# line_abu2.net
KiCad netlist of a schematic drawn in Altium Designer
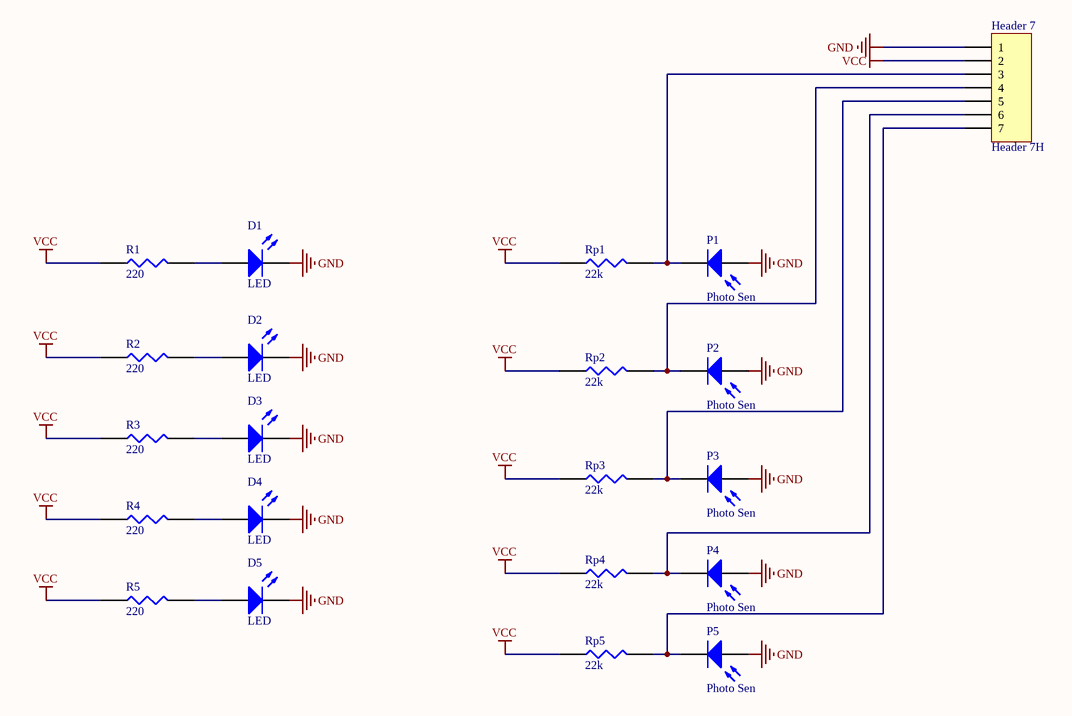
[diagram p0: line abu2.SchDoc]

(export (version "E")
  (design (tool "Eeschema 10.0.6"))
  (components
    (comp (ref "D1")
      (value "LED")
      (footprint "My_LED3MM")
      (description "Typical INFRARED GaAs LED")
      (fields (field (name "PUBLISHER") "Altium Limited"))
      (libsource (lib "Mylib") (part "LED"))
    )
    (comp (ref "D2")
      (value "LED")
      (footprint "My_LED3MM")
      (description "Typical INFRARED GaAs LED")
      (fields (field (name "PUBLISHER") "Altium Limited"))
      (libsource (lib "Mylib") (part "LED"))
    )
    (comp (ref "D3")
      (value "LED")
      (footprint "My_LED3MM")
      (description "Typical INFRARED GaAs LED")
      (fields (field (name "PUBLISHER") "Altium Limited"))
      (libsource (lib "Mylib") (part "LED"))
    )
    (comp (ref "D4")
      (value "LED")
      (footprint "My_LED3MM")
      (description "Typical INFRARED GaAs LED")
      (fields (field (name "PUBLISHER") "Altium Limited"))
      (libsource (lib "Mylib") (part "LED"))
    )
    (comp (ref "D5")
      (value "LED")
      (footprint "My_LED3MM")
      (description "Typical INFRARED GaAs LED")
      (fields (field (name "PUBLISHER") "Altium Limited"))
      (libsource (lib "Mylib") (part "LED"))
    )
    (comp (ref "Header 7")
      (value "Header 7H")
      (footprint "HDR1X7H")
      (description "Header, 7-Pin, Right Angle")
      (fields (field (name "PUBLISHER") "Altium Limited"))
      (libsource (lib "Miscellaneous Connectors") (part "Header 7H"))
    )
    (comp (ref "P1")
      (value "Photo Sen")
      (footprint "PIN2")
      (description "Photosensitive Diode")
      (fields (field (name "PUBLISHER") "Altium Limited"))
      (libsource (lib "Miscellaneous Devices") (part "Photo Sen"))
    )
    (comp (ref "P2")
      (value "Photo Sen")
      (footprint "PIN2")
      (description "Photosensitive Diode")
      (fields (field (name "PUBLISHER") "Altium Limited"))
      (libsource (lib "Miscellaneous Devices") (part "Photo Sen"))
    )
    (comp (ref "P3")
      (value "Photo Sen")
      (footprint "PIN2")
      (description "Photosensitive Diode")
      (fields (field (name "PUBLISHER") "Altium Limited"))
      (libsource (lib "Miscellaneous Devices") (part "Photo Sen"))
    )
    (comp (ref "P4")
      (value "Photo Sen")
      (footprint "PIN2")
      (description "Photosensitive Diode")
      (fields (field (name "PUBLISHER") "Altium Limited"))
      (libsource (lib "Miscellaneous Devices") (part "Photo Sen"))
    )
    (comp (ref "P5")
      (value "Photo Sen")
      (footprint "PIN2")
      (description "Photosensitive Diode")
      (fields (field (name "PUBLISHER") "Altium Limited"))
      (libsource (lib "Miscellaneous Devices") (part "Photo Sen"))
    )
    (comp (ref "R1")
      (value "220")
      (footprint "My_axial-0.4")
      (description "resistor 1/4 wat")
      (fields (field (name "Comment") "1k"))
      (libsource (lib "Mylib") (part "Res"))
    )
    (comp (ref "R2")
      (value "220")
      (footprint "My_axial-0.4")
      (description "resistor 1/4 wat")
      (fields (field (name "Comment") "1k"))
      (libsource (lib "Mylib") (part "Res"))
    )
    (comp (ref "R3")
      (value "220")
      (footprint "My_axial-0.4")
      (description "resistor 1/4 wat")
      (fields (field (name "Comment") "1k"))
      (libsource (lib "Mylib") (part "Res"))
    )
    (comp (ref "R4")
      (value "220")
      (footprint "My_axial-0.4")
      (description "resistor 1/4 wat")
      (fields (field (name "Comment") "1k"))
      (libsource (lib "Mylib") (part "Res"))
    )
    (comp (ref "R5")
      (value "220")
      (footprint "My_axial-0.4")
      (description "resistor 1/4 wat")
      (fields (field (name "Comment") "1k"))
      (libsource (lib "Mylib") (part "Res"))
    )
    (comp (ref "Rp1")
      (value "22k")
      (footprint "My_axial-0.4")
      (description "resistor 1/4 wat")
      (fields (field (name "Comment") "1k"))
      (libsource (lib "Mylib") (part "Res"))
    )
    (comp (ref "Rp2")
      (value "22k")
      (footprint "My_axial-0.4")
      (description "resistor 1/4 wat")
      (fields (field (name "Comment") "1k"))
      (libsource (lib "Mylib") (part "Res"))
    )
    (comp (ref "Rp3")
      (value "22k")
      (footprint "My_axial-0.4")
      (description "resistor 1/4 wat")
      (fields (field (name "Comment") "1k"))
      (libsource (lib "Mylib") (part "Res"))
    )
    (comp (ref "Rp4")
      (value "22k")
      (footprint "My_axial-0.4")
      (description "resistor 1/4 wat")
      (fields (field (name "Comment") "1k"))
      (libsource (lib "Mylib") (part "Res"))
    )
    (comp (ref "Rp5")
      (value "22k")
      (footprint "My_axial-0.4")
      (description "resistor 1/4 wat")
      (fields (field (name "Comment") "1k"))
      (libsource (lib "Mylib") (part "Res"))
    )
  )
  (nets
    (net (code "1") (name "GND") (class "Default")
      (node (ref "D1") (pin "K") (pinfunction "K_K") (pintype "passive"))
      (node (ref "D2") (pin "K") (pinfunction "K_K") (pintype "passive"))
      (node (ref "D3") (pin "K") (pinfunction "K_K") (pintype "passive"))
      (node (ref "D4") (pin "K") (pinfunction "K_K") (pintype "passive"))
      (node (ref "D5") (pin "K") (pinfunction "K_K") (pintype "passive"))
      (node (ref "Header 7") (pin "1") (pinfunction "1_1") (pintype "passive"))
      (node (ref "P1") (pin "1") (pinfunction "A_1") (pintype "passive"))
      (node (ref "P2") (pin "1") (pinfunction "A_1") (pintype "passive"))
      (node (ref "P3") (pin "1") (pinfunction "A_1") (pintype "passive"))
      (node (ref "P4") (pin "1") (pinfunction "A_1") (pintype "passive"))
      (node (ref "P5") (pin "1") (pinfunction "A_1") (pintype "passive"))
    )
    (net (code "2") (name "Net-(D1-PadA)") (class "Default")
      (node (ref "D1") (pin "A") (pinfunction "A_A") (pintype "passive"))
      (node (ref "R1") (pin "2") (pinfunction "2_2") (pintype "passive"))
    )
    (net (code "3") (name "Net-(D2-PadA)") (class "Default")
      (node (ref "D2") (pin "A") (pinfunction "A_A") (pintype "passive"))
      (node (ref "R2") (pin "2") (pinfunction "2_2") (pintype "passive"))
    )
    (net (code "4") (name "Net-(D3-PadA)") (class "Default")
      (node (ref "D3") (pin "A") (pinfunction "A_A") (pintype "passive"))
      (node (ref "R3") (pin "2") (pinfunction "2_2") (pintype "passive"))
    )
    (net (code "5") (name "Net-(D4-PadA)") (class "Default")
      (node (ref "D4") (pin "A") (pinfunction "A_A") (pintype "passive"))
      (node (ref "R4") (pin "2") (pinfunction "2_2") (pintype "passive"))
    )
    (net (code "6") (name "Net-(D5-PadA)") (class "Default")
      (node (ref "D5") (pin "A") (pinfunction "A_A") (pintype "passive"))
      (node (ref "R5") (pin "2") (pinfunction "2_2") (pintype "passive"))
    )
    (net (code "7") (name "Net-(P1-K)") (class "Default")
      (node (ref "Header 7") (pin "3") (pinfunction "3_3") (pintype "passive"))
      (node (ref "P1") (pin "2") (pinfunction "K_2") (pintype "passive"))
      (node (ref "Rp1") (pin "2") (pinfunction "2_2") (pintype "passive"))
    )
    (net (code "8") (name "Net-(P2-K)") (class "Default")
      (node (ref "Header 7") (pin "4") (pinfunction "4_4") (pintype "passive"))
      (node (ref "P2") (pin "2") (pinfunction "K_2") (pintype "passive"))
      (node (ref "Rp2") (pin "2") (pinfunction "2_2") (pintype "passive"))
    )
    (net (code "9") (name "Net-(P3-K)") (class "Default")
      (node (ref "Header 7") (pin "5") (pinfunction "5_5") (pintype "passive"))
      (node (ref "P3") (pin "2") (pinfunction "K_2") (pintype "passive"))
      (node (ref "Rp3") (pin "2") (pinfunction "2_2") (pintype "passive"))
    )
    (net (code "10") (name "Net-(P4-K)") (class "Default")
      (node (ref "Header 7") (pin "6") (pinfunction "6_6") (pintype "passive"))
      (node (ref "P4") (pin "2") (pinfunction "K_2") (pintype "passive"))
      (node (ref "Rp4") (pin "2") (pinfunction "2_2") (pintype "passive"))
    )
    (net (code "11") (name "Net-(P5-K)") (class "Default")
      (node (ref "Header 7") (pin "7") (pinfunction "7_7") (pintype "passive"))
      (node (ref "P5") (pin "2") (pinfunction "K_2") (pintype "passive"))
      (node (ref "Rp5") (pin "2") (pinfunction "2_2") (pintype "passive"))
    )
    (net (code "12") (name "VCC") (class "Default")
      (node (ref "Header 7") (pin "2") (pinfunction "2_2") (pintype "passive"))
      (node (ref "R1") (pin "1") (pinfunction "1_1") (pintype "passive"))
      (node (ref "R2") (pin "1") (pinfunction "1_1") (pintype "passive"))
      (node (ref "R3") (pin "1") (pinfunction "1_1") (pintype "passive"))
      (node (ref "R4") (pin "1") (pinfunction "1_1") (pintype "passive"))
      (node (ref "R5") (pin "1") (pinfunction "1_1") (pintype "passive"))
      (node (ref "Rp1") (pin "1") (pinfunction "1_1") (pintype "passive"))
      (node (ref "Rp2") (pin "1") (pinfunction "1_1") (pintype "passive"))
      (node (ref "Rp3") (pin "1") (pinfunction "1_1") (pintype "passive"))
      (node (ref "Rp4") (pin "1") (pinfunction "1_1") (pintype "passive"))
      (node (ref "Rp5") (pin "1") (pinfunction "1_1") (pintype "passive"))
    )
  )
)
